# LEDs.net
KiCad netlist of a schematic drawn in Altium Designer
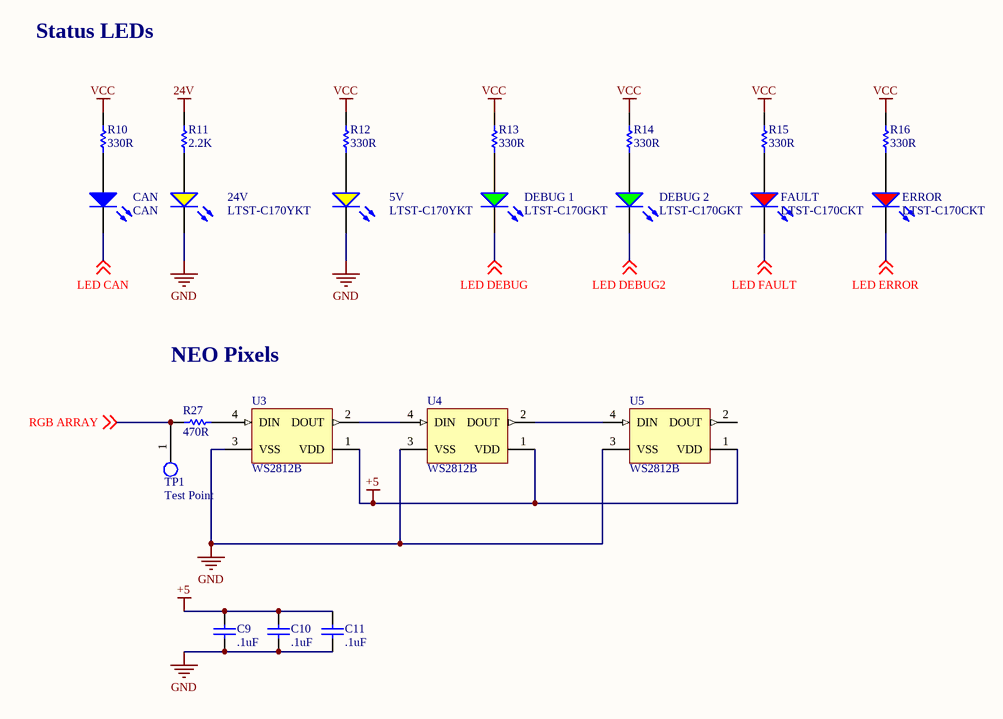
[diagram p0: LEDs.SchDoc]

(export (version "E")
  (design (tool "Eeschema 10.0.6"))
  (components
    (comp (ref "5V")
      (value "LTST-C170YKT")
      (footprint "LTST-C170YKT_V")
      (description "LED Uni-Color Yellow, 60 mW, 80 mA, -55 to 85 degC, 2-Pin SMD, RoHS, Tape and Reel")
      (fields (field (name "MANUFACTURER") "Lite-On"))
      (libsource (lib "Altium Content Vault") (part "LED-YELLOW-AK-2"))
    )
    (comp (ref "24V")
      (value "LTST-C170YKT")
      (footprint "LTST-C170YKT_V")
      (description "LED Uni-Color Yellow, 60 mW, 80 mA, -55 to 85 degC, 2-Pin SMD, RoHS, Tape and Reel")
      (fields (field (name "MANUFACTURER") "Lite-On"))
      (libsource (lib "Altium Content Vault") (part "LED-YELLOW-AK-2"))
    )
    (comp (ref "C9")
      (value ".1uF")
      (footprint "CAPC0805(2012)130_N")
      (description "CAP 390pF 200V ±5% 0805 (2012 Metric) Thickness 1.3mm SMD")
      (fields (field (name "TOLERANCE") "Â±5%"))
      (libsource (lib "Altium Content Vault") (part "CAP"))
    )
    (comp (ref "C10")
      (value ".1uF")
      (footprint "CAPC0805(2012)130_N")
      (description "CAP 390pF 200V ±5% 0805 (2012 Metric) Thickness 1.3mm SMD")
      (fields (field (name "TOLERANCE") "Â±5%"))
      (libsource (lib "Altium Content Vault") (part "CAP"))
    )
    (comp (ref "C11")
      (value ".1uF")
      (footprint "CAPC0805(2012)130_N")
      (description "CAP 390pF 200V ±5% 0805 (2012 Metric) Thickness 1.3mm SMD")
      (fields (field (name "TOLERANCE") "Â±5%"))
      (libsource (lib "Altium Content Vault") (part "CAP"))
    )
    (comp (ref "CAN")
      (value "CAN")
      (footprint "0805_A")
      (description "SMD mono-color Chip LED, WL-SMCW, Blue")
      (fields (field (name "MANUFACTURER") "Wuerth Elektronik") (field (name "PARTNUMBER") "150080BS75000"))
      (libsource (lib "Altium Content Vault") (part "WE-LED_K1A2-2"))
    )
    (comp (ref "DEBUG 1")
      (value "LTST-C170GKT")
      (footprint "LTST-C170GKT_V")
      (description "LED Uni-Color Green, 100 mW, 120 mA, -55 to 85 degC, 2-Pin SMD, RoHS, Tape and Reel")
      (fields (field (name "MANUFACTURER") "Lite-On"))
      (libsource (lib "Altium Content Vault") (part "LED-GREEN-AK-2"))
    )
    (comp (ref "DEBUG 2")
      (value "LTST-C170GKT")
      (footprint "LTST-C170GKT_V")
      (description "LED Uni-Color Green, 100 mW, 120 mA, -55 to 85 degC, 2-Pin SMD, RoHS, Tape and Reel")
      (fields (field (name "MANUFACTURER") "Lite-On"))
      (libsource (lib "Altium Content Vault") (part "LED-GREEN-AK-2"))
    )
    (comp (ref "ERROR")
      (value "LTST-C170CKT")
      (footprint "LTST-C170CKT_V")
      (description "LED Uni-Color Red, 100 mW, 200 mA, -55 to 85 degC, 2-Pin SMD, RoHS, Tape and Reel")
      (fields (field (name "MANUFACTURER") "Lite-On"))
      (libsource (lib "Altium Content Vault") (part "LED-RED-AK-2"))
    )
    (comp (ref "FAULT")
      (value "LTST-C170CKT")
      (footprint "LTST-C170CKT_V")
      (description "LED Uni-Color Red, 100 mW, 200 mA, -55 to 85 degC, 2-Pin SMD, RoHS, Tape and Reel")
      (fields (field (name "MANUFACTURER") "Lite-On"))
      (libsource (lib "Altium Content Vault") (part "LED-RED-AK-2"))
    )
    (comp (ref "R10")
      (value "330R")
      (footprint "RESC0805(2012)_N")
      (description "120R 0.125W 5% 0805 (2012 Metric)  SMD")
      (fields (field (name "TOLERANCE") "5 %") (field (name "POWER") "0.125 W"))
      (libsource (lib "Husky Robotics Standard Library 2019-2020") (part "120R 5% 0805"))
    )
    (comp (ref "R11")
      (value "2.2K")
      (footprint "RESC0805(2012)_N")
      (description "120R 0.125W 5% 0805 (2012 Metric)  SMD")
      (fields (field (name "TOLERANCE") "5 %") (field (name "POWER") "0.125 W"))
      (libsource (lib "Husky Robotics Standard Library 2019-2020") (part "120R 5% 0805"))
    )
    (comp (ref "R12")
      (value "330R")
      (footprint "RESC0805(2012)_N")
      (description "120R 0.125W 5% 0805 (2012 Metric)  SMD")
      (fields (field (name "TOLERANCE") "5 %") (field (name "POWER") "0.125 W"))
      (libsource (lib "Husky Robotics Standard Library 2019-2020") (part "120R 5% 0805"))
    )
    (comp (ref "R13")
      (value "330R")
      (footprint "RESC0805(2012)_N")
      (description "120R 0.125W 5% 0805 (2012 Metric)  SMD")
      (fields (field (name "TOLERANCE") "5 %") (field (name "POWER") "0.125 W"))
      (libsource (lib "Husky Robotics Standard Library 2019-2020") (part "120R 5% 0805"))
    )
    (comp (ref "R14")
      (value "330R")
      (footprint "RESC0805(2012)_N")
      (description "120R 0.125W 5% 0805 (2012 Metric)  SMD")
      (fields (field (name "TOLERANCE") "5 %") (field (name "POWER") "0.125 W"))
      (libsource (lib "Husky Robotics Standard Library 2019-2020") (part "120R 5% 0805"))
    )
    (comp (ref "R15")
      (value "330R")
      (footprint "RESC0805(2012)_N")
      (description "120R 0.125W 5% 0805 (2012 Metric)  SMD")
      (fields (field (name "TOLERANCE") "5 %") (field (name "POWER") "0.125 W"))
      (libsource (lib "Husky Robotics Standard Library 2019-2020") (part "120R 5% 0805"))
    )
    (comp (ref "R16")
      (value "330R")
      (footprint "RESC0805(2012)_N")
      (description "120R 0.125W 5% 0805 (2012 Metric)  SMD")
      (fields (field (name "TOLERANCE") "5 %") (field (name "POWER") "0.125 W"))
      (libsource (lib "Husky Robotics Standard Library 2019-2020") (part "120R 5% 0805"))
    )
    (comp (ref "R27")
      (value "470R")
      (footprint "RESC0805(2012)_N")
      (description "120R 0.125W 5% 0805 (2012 Metric)  SMD")
      (fields (field (name "TOLERANCE") "5 %") (field (name "POWER") "0.125 W"))
      (libsource (lib "Husky Robotics Standard Library 2019-2020") (part "120R 5% 0805"))
    )
    (comp (ref "TP1")
      (value "Test Point")
      (footprint "Test Point Through-hole")
      (libsource (lib "Husky Robotics Standard Library 2019-2020") (part "Test Point"))
    )
    (comp (ref "U3")
      (value "WS2812B")
      (footprint "ADAI-WS2812B_V")
      (fields (field (name "TOLERANCE") "10%"))
      (libsource (lib "Altium Content Vault") (part "ADAI-WS2812B-4"))
    )
    (comp (ref "U4")
      (value "WS2812B")
      (footprint "ADAI-WS2812B_V")
      (fields (field (name "TOLERANCE") "10%"))
      (libsource (lib "Altium Content Vault") (part "ADAI-WS2812B-4"))
    )
    (comp (ref "U5")
      (value "WS2812B")
      (footprint "ADAI-WS2812B_V")
      (fields (field (name "TOLERANCE") "10%"))
      (libsource (lib "Altium Content Vault") (part "ADAI-WS2812B-4"))
    )
  )
  (nets
    (net (code "1") (name "+5") (class "Default")
      (node (ref "C10") (pin "2") (pinfunction "2_2") (pintype "passive"))
      (node (ref "C11") (pin "2") (pinfunction "2_2") (pintype "passive"))
      (node (ref "C9") (pin "2") (pinfunction "2_2") (pintype "passive"))
      (node (ref "U3") (pin "1") (pinfunction "VDD_1") (pintype "power_in"))
      (node (ref "U4") (pin "1") (pinfunction "VDD_1") (pintype "power_in"))
      (node (ref "U5") (pin "1") (pinfunction "VDD_1") (pintype "power_in"))
    )
    (net (code "2") (name "24V") (class "Default")
      (node (ref "R11") (pin "2") (pinfunction "2_2") (pintype "passive"))
    )
    (net (code "3") (name "GND") (class "Default")
      (node (ref "24V") (pin "2") (pinfunction "K_2") (pintype "passive"))
      (node (ref "5V") (pin "2") (pinfunction "K_2") (pintype "passive"))
      (node (ref "C10") (pin "1") (pinfunction "1_1") (pintype "passive"))
      (node (ref "C11") (pin "1") (pinfunction "1_1") (pintype "passive"))
      (node (ref "C9") (pin "1") (pinfunction "1_1") (pintype "passive"))
      (node (ref "U3") (pin "3") (pinfunction "VSS_3") (pintype "power_in"))
      (node (ref "U4") (pin "3") (pinfunction "VSS_3") (pintype "power_in"))
      (node (ref "U5") (pin "3") (pinfunction "VSS_3") (pintype "power_in"))
    )
    (net (code "4") (name "LED CAN") (class "Default")
      (node (ref "CAN") (pin "1") (pinfunction "K_1") (pintype "passive"))
    )
    (net (code "5") (name "LED DEBUG") (class "Default")
      (node (ref "DEBUG 1") (pin "2") (pinfunction "K_2") (pintype "passive"))
    )
    (net (code "6") (name "LED DEBUG2") (class "Default")
      (node (ref "DEBUG 2") (pin "2") (pinfunction "K_2") (pintype "passive"))
    )
    (net (code "7") (name "LED ERROR") (class "Default")
      (node (ref "ERROR") (pin "2") (pinfunction "K_2") (pintype "passive"))
    )
    (net (code "8") (name "LED FAULT") (class "Default")
      (node (ref "FAULT") (pin "2") (pinfunction "K_2") (pintype "passive"))
    )
    (net (code "9") (name "Net-(5V-A)") (class "Default")
      (node (ref "5V") (pin "1") (pinfunction "A_1") (pintype "passive"))
      (node (ref "R12") (pin "1") (pinfunction "1_1") (pintype "passive"))
    )
    (net (code "10") (name "Net-(24V-A)") (class "Default")
      (node (ref "24V") (pin "1") (pinfunction "A_1") (pintype "passive"))
      (node (ref "R11") (pin "1") (pinfunction "1_1") (pintype "passive"))
    )
    (net (code "11") (name "Net-(CAN-A)") (class "Default")
      (node (ref "CAN") (pin "2") (pinfunction "A_2") (pintype "passive"))
      (node (ref "R10") (pin "1") (pinfunction "1_1") (pintype "passive"))
    )
    (net (code "12") (name "Net-(DEBUG 1-A)") (class "Default")
      (node (ref "DEBUG 1") (pin "1") (pinfunction "A_1") (pintype "passive"))
      (node (ref "R13") (pin "1") (pinfunction "1_1") (pintype "passive"))
    )
    (net (code "13") (name "Net-(DEBUG 2-A)") (class "Default")
      (node (ref "DEBUG 2") (pin "1") (pinfunction "A_1") (pintype "passive"))
      (node (ref "R14") (pin "1") (pinfunction "1_1") (pintype "passive"))
    )
    (net (code "14") (name "Net-(ERROR-A)") (class "Default")
      (node (ref "ERROR") (pin "1") (pinfunction "A_1") (pintype "passive"))
      (node (ref "R16") (pin "1") (pinfunction "1_1") (pintype "passive"))
    )
    (net (code "15") (name "Net-(FAULT-A)") (class "Default")
      (node (ref "FAULT") (pin "1") (pinfunction "A_1") (pintype "passive"))
      (node (ref "R15") (pin "1") (pinfunction "1_1") (pintype "passive"))
    )
    (net (code "16") (name "Net-(U3-DIN)") (class "Default")
      (node (ref "R27") (pin "2") (pinfunction "2_2") (pintype "passive"))
      (node (ref "U3") (pin "4") (pinfunction "DIN_4") (pintype "input"))
    )
    (net (code "17") (name "Net-(U3-DOUT)") (class "Default")
      (node (ref "U3") (pin "2") (pinfunction "DOUT_2") (pintype "output"))
      (node (ref "U4") (pin "4") (pinfunction "DIN_4") (pintype "input"))
    )
    (net (code "18") (name "Net-(U4-DOUT)") (class "Default")
      (node (ref "U4") (pin "2") (pinfunction "DOUT_2") (pintype "output"))
      (node (ref "U5") (pin "4") (pinfunction "DIN_4") (pintype "input"))
    )
    (net (code "19") (name "RGB ARRAY") (class "Default")
      (node (ref "R27") (pin "1") (pinfunction "1_1") (pintype "passive"))
      (node (ref "TP1") (pin "1") (pinfunction "1_1") (pintype "passive"))
    )
    (net (code "20") (name "VCC") (class "Default")
      (node (ref "R10") (pin "2") (pinfunction "2_2") (pintype "passive"))
      (node (ref "R12") (pin "2") (pinfunction "2_2") (pintype "passive"))
      (node (ref "R13") (pin "2") (pinfunction "2_2") (pintype "passive"))
      (node (ref "R14") (pin "2") (pinfunction "2_2") (pintype "passive"))
      (node (ref "R15") (pin "2") (pinfunction "2_2") (pintype "passive"))
      (node (ref "R16") (pin "2") (pinfunction "2_2") (pintype "passive"))
    )
    (net (code "21") (name "unconnected-(U5-DOUT-Pad2)") (class "Default")
      (node (ref "U5") (pin "2") (pinfunction "DOUT_2") (pintype "output"))
    )
  )
)
